# 24L01S.net
KiCad netlist of a schematic drawn in Altium Designer
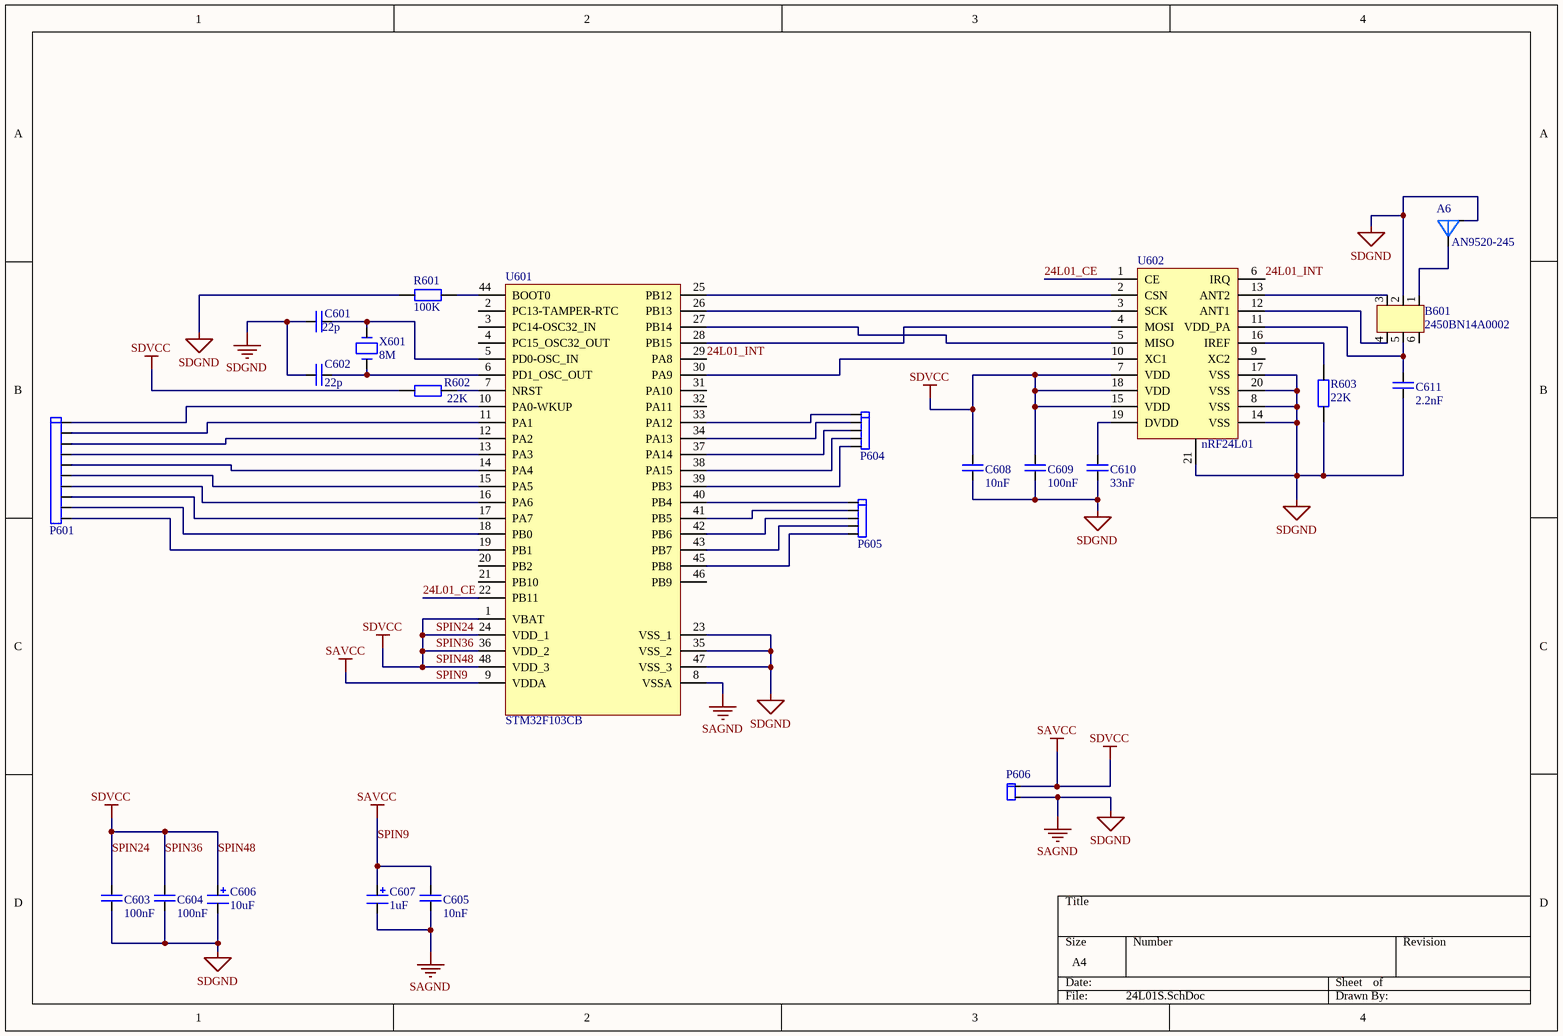
[diagram p0: 24L01S.SchDoc]

(export (version "E")
  (design (tool "Eeschema 10.0.6"))
  (components
    (comp (ref "A6")
      (value "AN9520-245")
      (footprint "AN9520-245")
      (description "antenna")
      (libsource (lib "Library") (part "AN9520-245"))
    )
    (comp (ref "B601")
      (value "2450BN14A0002")
      (footprint "2450BM14A0002")
      (description "nRF24L01")
      (libsource (lib "Library") (part "2450BN14A0002"))
    )
    (comp (ref "C601") (value "22p") (footprint "0603") (libsource (lib "Library") (part "C0603")))
    (comp (ref "C602") (value "22p") (footprint "0603") (libsource (lib "Library") (part "C0603")))
    (comp (ref "C603") (value "100nF") (footprint "0603") (libsource (lib "Library") (part "C0603")))
    (comp (ref "C604") (value "100nF") (footprint "0603") (libsource (lib "Library") (part "C0603")))
    (comp (ref "C605") (value "10nF") (footprint "0603") (libsource (lib "Library") (part "C0603")))
    (comp (ref "C606") (value "10uF") (footprint "0805") (libsource (lib "Library") (part "C0805")))
    (comp (ref "C607") (value "1uF") (footprint "0805") (libsource (lib "Library") (part "C0805")))
    (comp (ref "C608") (value "10nF") (footprint "0603") (libsource (lib "Library") (part "C0603")))
    (comp (ref "C609") (value "100nF") (footprint "0603") (libsource (lib "Library") (part "C0603")))
    (comp (ref "C610") (value "33nF") (footprint "0603") (libsource (lib "Library") (part "C0603")))
    (comp (ref "C611") (value "2.2nF") (footprint "0603") (libsource (lib "Library") (part "C0603")))
    (comp (ref "P601")
      (value "DIP10_1.27mm")
      (footprint "DIP10_1.27mm")
      (libsource (lib "Library") (part "DIP10_1.27mm"))
    )
    (comp (ref "P604")
      (value "DIP_5_1.27mm")
      (footprint "DIP_5_1.27mm")
      (libsource (lib "Library") (part "DIP_5_1.27mm"))
    )
    (comp (ref "P605")
      (value "DIP_5_1.27mm")
      (footprint "DIP_5_1.27mm")
      (libsource (lib "Library") (part "DIP_5_1.27mm"))
    )
    (comp (ref "P606") (value "DIP_2") (footprint "DIP_2") (libsource (lib "Library") (part "DIP_2")))
    (comp (ref "R601") (value "100K") (footprint "0603") (libsource (lib "Library") (part "R0603")))
    (comp (ref "R602") (value "22K") (footprint "0603") (libsource (lib "Library") (part "R0603")))
    (comp (ref "R603") (value "22K") (footprint "0603") (libsource (lib "Library") (part "R0603")))
    (comp (ref "U601")
      (value "STM32F103CB")
      (footprint "LQFP48")
      (libsource (lib "Library") (part "STM32F103CB"))
    )
    (comp (ref "U602")
      (value "nRF24L01")
      (footprint "nRF24L01")
      (libsource (lib "Library") (part "nRF24L01"))
    )
    (comp (ref "X601") (value "8M") (footprint "X1") (libsource (lib "Library") (part "X1")))
  )
  (nets
    (net (code "1") (name "/24L01_CE") (class "Default")
      (node (ref "U601") (pin "22") (pinfunction "PB11_22") (pintype "passive"))
      (node (ref "U602") (pin "1") (pinfunction "CE_1") (pintype "passive"))
    )
    (net (code "2") (name "/24L01_INT") (class "Default")
      (node (ref "U601") (pin "29") (pinfunction "PA8_29") (pintype "passive"))
      (node (ref "U602") (pin "6") (pinfunction "IRQ_6") (pintype "passive"))
    )
    (net (code "3") (name "Net-(A6-Pad1)") (class "Default")
      (node (ref "A6") (pin "1") (pinfunction "1_1") (pintype "passive"))
      (node (ref "B601") (pin "1") (pinfunction "1_1") (pintype "passive"))
    )
    (net (code "4") (name "Net-(U601-BOOT0)") (class "Default")
      (node (ref "R601") (pin "2") (pinfunction "2_2") (pintype "passive"))
      (node (ref "U601") (pin "44") (pinfunction "BOOT0_44") (pintype "passive"))
    )
    (net (code "5") (name "Net-(U601-NRST)") (class "Default")
      (node (ref "R602") (pin "1") (pinfunction "1_1") (pintype "passive"))
      (node (ref "U601") (pin "7") (pinfunction "NRST_7") (pintype "passive"))
    )
    (net (code "6") (name "Net-(U601-PA0-WKUP)") (class "Default")
      (node (ref "P601") (pin "1") (pintype "passive"))
      (node (ref "U601") (pin "10") (pinfunction "PA0-WKUP_10") (pintype "passive"))
    )
    (net (code "7") (name "Net-(U601-PA1)") (class "Default")
      (node (ref "P601") (pin "2") (pintype "passive"))
      (node (ref "U601") (pin "11") (pinfunction "PA1_11") (pintype "passive"))
    )
    (net (code "8") (name "Net-(U601-PA2)") (class "Default")
      (node (ref "P601") (pin "3") (pintype "passive"))
      (node (ref "U601") (pin "12") (pinfunction "PA2_12") (pintype "passive"))
    )
    (net (code "9") (name "Net-(U601-PA3)") (class "Default")
      (node (ref "P601") (pin "4") (pintype "passive"))
      (node (ref "U601") (pin "13") (pinfunction "PA3_13") (pintype "passive"))
    )
    (net (code "10") (name "Net-(U601-PA4)") (class "Default")
      (node (ref "P601") (pin "5") (pintype "passive"))
      (node (ref "U601") (pin "14") (pinfunction "PA4_14") (pintype "passive"))
    )
    (net (code "11") (name "Net-(U601-PA5)") (class "Default")
      (node (ref "P601") (pin "6") (pintype "passive"))
      (node (ref "U601") (pin "15") (pinfunction "PA5_15") (pintype "passive"))
    )
    (net (code "12") (name "Net-(U601-PA6)") (class "Default")
      (node (ref "P601") (pin "7") (pintype "passive"))
      (node (ref "U601") (pin "16") (pinfunction "PA6_16") (pintype "passive"))
    )
    (net (code "13") (name "Net-(U601-PA7)") (class "Default")
      (node (ref "P601") (pin "8") (pintype "passive"))
      (node (ref "U601") (pin "17") (pinfunction "PA7_17") (pintype "passive"))
    )
    (net (code "14") (name "Net-(U601-PA9)") (class "Default")
      (node (ref "U601") (pin "30") (pinfunction "PA9_30") (pintype "passive"))
      (node (ref "U602") (pin "10") (pinfunction "XC1_10") (pintype "passive"))
    )
    (net (code "15") (name "Net-(U601-PA12)") (class "Default")
      (node (ref "P604") (pin "1") (pintype "passive"))
      (node (ref "U601") (pin "33") (pinfunction "PA12_33") (pintype "passive"))
    )
    (net (code "16") (name "Net-(U601-PA13)") (class "Default")
      (node (ref "P604") (pin "2") (pintype "passive"))
      (node (ref "U601") (pin "34") (pinfunction "PA13_34") (pintype "passive"))
    )
    (net (code "17") (name "Net-(U601-PA14)") (class "Default")
      (node (ref "P604") (pin "3") (pintype "passive"))
      (node (ref "U601") (pin "37") (pinfunction "PA14_37") (pintype "passive"))
    )
    (net (code "18") (name "Net-(U601-PA15)") (class "Default")
      (node (ref "P604") (pin "4") (pintype "passive"))
      (node (ref "U601") (pin "38") (pinfunction "PA15_38") (pintype "passive"))
    )
    (net (code "19") (name "Net-(U601-PB0)") (class "Default")
      (node (ref "P601") (pin "9") (pintype "passive"))
      (node (ref "U601") (pin "18") (pinfunction "PB0_18") (pintype "passive"))
    )
    (net (code "20") (name "Net-(U601-PB1)") (class "Default")
      (node (ref "P601") (pin "10") (pintype "passive"))
      (node (ref "U601") (pin "19") (pinfunction "PB1_19") (pintype "passive"))
    )
    (net (code "21") (name "Net-(U601-PB3)") (class "Default")
      (node (ref "P604") (pin "5") (pintype "passive"))
      (node (ref "U601") (pin "39") (pinfunction "PB3_39") (pintype "passive"))
    )
    (net (code "22") (name "Net-(U601-PB4)") (class "Default")
      (node (ref "P605") (pin "1") (pintype "passive"))
      (node (ref "U601") (pin "40") (pinfunction "PB4_40") (pintype "passive"))
    )
    (net (code "23") (name "Net-(U601-PB5)") (class "Default")
      (node (ref "P605") (pin "2") (pintype "passive"))
      (node (ref "U601") (pin "41") (pinfunction "PB5_41") (pintype "passive"))
    )
    (net (code "24") (name "Net-(U601-PB6)") (class "Default")
      (node (ref "P605") (pin "3") (pintype "passive"))
      (node (ref "U601") (pin "42") (pinfunction "PB6_42") (pintype "passive"))
    )
    (net (code "25") (name "Net-(U601-PB7)") (class "Default")
      (node (ref "P605") (pin "4") (pintype "passive"))
      (node (ref "U601") (pin "43") (pinfunction "PB7_43") (pintype "passive"))
    )
    (net (code "26") (name "Net-(U601-PB8)") (class "Default")
      (node (ref "P605") (pin "5") (pintype "passive"))
      (node (ref "U601") (pin "45") (pinfunction "PB8_45") (pintype "passive"))
    )
    (net (code "27") (name "Net-(U601-PB12)") (class "Default")
      (node (ref "U601") (pin "25") (pinfunction "PB12_25") (pintype "passive"))
      (node (ref "U602") (pin "2") (pinfunction "CSN_2") (pintype "passive"))
    )
    (net (code "28") (name "Net-(U601-PB13)") (class "Default")
      (node (ref "U601") (pin "26") (pinfunction "PB13_26") (pintype "passive"))
      (node (ref "U602") (pin "3") (pinfunction "SCK_3") (pintype "passive"))
    )
    (net (code "29") (name "Net-(U601-PB14)") (class "Default")
      (node (ref "U601") (pin "27") (pinfunction "PB14_27") (pintype "passive"))
      (node (ref "U602") (pin "5") (pinfunction "MISO_5") (pintype "passive"))
    )
    (net (code "30") (name "Net-(U601-PB15)") (class "Default")
      (node (ref "U601") (pin "28") (pinfunction "PB15_28") (pintype "passive"))
      (node (ref "U602") (pin "4") (pinfunction "MOSI_4") (pintype "passive"))
    )
    (net (code "31") (name "Net-(U601-PD0-OSC_IN)") (class "Default")
      (node (ref "C601") (pin "2") (pinfunction "2_2") (pintype "passive"))
      (node (ref "U601") (pin "5") (pinfunction "PD0-OSC_IN_5") (pintype "passive"))
      (node (ref "X601") (pin "2") (pinfunction "2_2") (pintype "passive"))
    )
    (net (code "32") (name "Net-(U601-PD1_OSC_OUT)") (class "Default")
      (node (ref "C602") (pin "2") (pinfunction "2_2") (pintype "passive"))
      (node (ref "U601") (pin "6") (pinfunction "PD1_OSC_OUT_6") (pintype "passive"))
      (node (ref "X601") (pin "1") (pinfunction "1_1") (pintype "passive"))
    )
    (net (code "33") (name "Net-(U602-ANT1)") (class "Default")
      (node (ref "B601") (pin "4") (pinfunction "4_4") (pintype "passive"))
      (node (ref "U602") (pin "12") (pinfunction "ANT1_12") (pintype "passive"))
    )
    (net (code "34") (name "Net-(U602-ANT2)") (class "Default")
      (node (ref "B601") (pin "3") (pinfunction "3_3") (pintype "passive"))
      (node (ref "U602") (pin "13") (pinfunction "ANT2_13") (pintype "passive"))
    )
    (net (code "35") (name "Net-(U602-DVDD)") (class "Default")
      (node (ref "C610") (pin "2") (pinfunction "2_2") (pintype "passive"))
      (node (ref "U602") (pin "19") (pinfunction "DVDD_19") (pintype "passive"))
    )
    (net (code "36") (name "Net-(U602-IREF)") (class "Default")
      (node (ref "R603") (pin "1") (pinfunction "1_1") (pintype "passive"))
      (node (ref "U602") (pin "16") (pinfunction "IREF_16") (pintype "passive"))
    )
    (net (code "37") (name "Net-(U602-VDD_PA)") (class "Default")
      (node (ref "B601") (pin "5") (pinfunction "5_5") (pintype "passive"))
      (node (ref "C611") (pin "2") (pinfunction "2_2") (pintype "passive"))
      (node (ref "U602") (pin "11") (pinfunction "VDD_PA_11") (pintype "passive"))
    )
    (net (code "38") (name "SAGND") (class "Default")
      (node (ref "A6") (pin "2") (pinfunction "2_2") (pintype "passive"))
      (node (ref "B601") (pin "2") (pinfunction "2_2") (pintype "passive"))
      (node (ref "C601") (pin "1") (pinfunction "1_1") (pintype "passive"))
      (node (ref "C602") (pin "1") (pinfunction "1_1") (pintype "passive"))
      (node (ref "C603") (pin "1") (pinfunction "1_1") (pintype "passive"))
      (node (ref "C604") (pin "1") (pinfunction "1_1") (pintype "passive"))
      (node (ref "C605") (pin "1") (pinfunction "1_1") (pintype "passive"))
      (node (ref "C606") (pin "2") (pinfunction "2_2") (pintype "passive"))
      (node (ref "C607") (pin "2") (pinfunction "2_2") (pintype "passive"))
      (node (ref "C608") (pin "1") (pinfunction "1_1") (pintype "passive"))
      (node (ref "C609") (pin "1") (pinfunction "1_1") (pintype "passive"))
      (node (ref "C610") (pin "1") (pinfunction "1_1") (pintype "passive"))
      (node (ref "C611") (pin "1") (pinfunction "1_1") (pintype "passive"))
      (node (ref "P606") (pin "2") (pinfunction "2_2") (pintype "passive"))
      (node (ref "R601") (pin "1") (pinfunction "1_1") (pintype "passive"))
      (node (ref "R603") (pin "2") (pinfunction "2_2") (pintype "passive"))
      (node (ref "U601") (pin "23") (pinfunction "VSS_1_23") (pintype "passive"))
      (node (ref "U601") (pin "35") (pinfunction "VSS_2_35") (pintype "passive"))
      (node (ref "U601") (pin "47") (pinfunction "VSS_3_47") (pintype "passive"))
      (node (ref "U601") (pin "8") (pinfunction "VSSA_8") (pintype "passive"))
      (node (ref "U602") (pin "14") (pinfunction "VSS_14") (pintype "passive"))
      (node (ref "U602") (pin "17") (pinfunction "VSS_17") (pintype "passive"))
      (node (ref "U602") (pin "20") (pinfunction "VSS_20") (pintype "passive"))
      (node (ref "U602") (pin "21") (pintype "passive"))
      (node (ref "U602") (pin "8") (pinfunction "VSS_8") (pintype "passive"))
    )
    (net (code "39") (name "SAVCC") (class "Default")
      (node (ref "C603") (pin "2") (pinfunction "2_2") (pintype "passive"))
      (node (ref "C604") (pin "2") (pinfunction "2_2") (pintype "passive"))
      (node (ref "C605") (pin "2") (pinfunction "2_2") (pintype "passive"))
      (node (ref "C606") (pin "1") (pinfunction "1_1") (pintype "passive"))
      (node (ref "C607") (pin "1") (pinfunction "1_1") (pintype "passive"))
      (node (ref "C608") (pin "2") (pinfunction "2_2") (pintype "passive"))
      (node (ref "C609") (pin "2") (pinfunction "2_2") (pintype "passive"))
      (node (ref "P606") (pin "1") (pinfunction "1_1") (pintype "passive"))
      (node (ref "R602") (pin "2") (pinfunction "2_2") (pintype "passive"))
      (node (ref "U601") (pin "1") (pinfunction "VBAT_1") (pintype "passive"))
      (node (ref "U601") (pin "24") (pinfunction "VDD_1_24") (pintype "passive"))
      (node (ref "U601") (pin "36") (pinfunction "VDD_2_36") (pintype "passive"))
      (node (ref "U601") (pin "48") (pinfunction "VDD_3_48") (pintype "passive"))
      (node (ref "U601") (pin "9") (pinfunction "VDDA_9") (pintype "passive"))
      (node (ref "U602") (pin "15") (pinfunction "VDD_15") (pintype "passive"))
      (node (ref "U602") (pin "18") (pinfunction "VDD_18") (pintype "passive"))
      (node (ref "U602") (pin "7") (pinfunction "VDD_7") (pintype "passive"))
    )
    (net (code "40") (name "unconnected-(B601-Pad6)") (class "Default")
      (node (ref "B601") (pin "6") (pinfunction "6_6") (pintype "passive"))
    )
    (net (code "41") (name "unconnected-(U601-PA10-Pad31)") (class "Default")
      (node (ref "U601") (pin "31") (pinfunction "PA10_31") (pintype "passive"))
    )
    (net (code "42") (name "unconnected-(U601-PA11-Pad32)") (class "Default")
      (node (ref "U601") (pin "32") (pinfunction "PA11_32") (pintype "passive"))
    )
    (net (code "43") (name "unconnected-(U601-PB2-Pad20)") (class "Default")
      (node (ref "U601") (pin "20") (pinfunction "PB2_20") (pintype "passive"))
    )
    (net (code "44") (name "unconnected-(U601-PB9-Pad46)") (class "Default")
      (node (ref "U601") (pin "46") (pinfunction "PB9_46") (pintype "passive"))
    )
    (net (code "45") (name "unconnected-(U601-PB10-Pad21)") (class "Default")
      (node (ref "U601") (pin "21") (pinfunction "PB10_21") (pintype "passive"))
    )
    (net (code "46") (name "unconnected-(U601-PC13-TAMPER-RTC-Pad2)") (class "Default")
      (node (ref "U601") (pin "2") (pinfunction "PC13-TAMPER-RTC_2") (pintype "passive"))
    )
    (net (code "47") (name "unconnected-(U601-PC14-OSC32_IN-Pad3)") (class "Default")
      (node (ref "U601") (pin "3") (pinfunction "PC14-OSC32_IN_3") (pintype "passive"))
    )
    (net (code "48") (name "unconnected-(U601-PC15_OSC32_OUT-Pad4)") (class "Default")
      (node (ref "U601") (pin "4") (pinfunction "PC15_OSC32_OUT_4") (pintype "passive"))
    )
    (net (code "49") (name "unconnected-(U602-XC2-Pad9)") (class "Default")
      (node (ref "U602") (pin "9") (pinfunction "XC2_9") (pintype "passive"))
    )
  )
)
